# shell_2.net
KiCad netlist of a schematic drawn in EAGLE
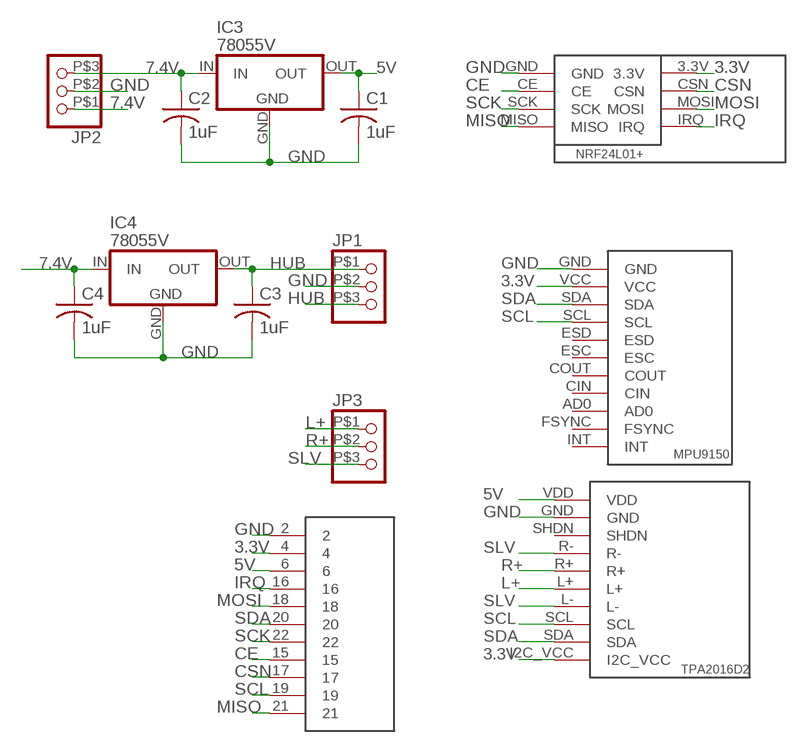
[diagram p0: schematic, sheet 1]

(export (version "E")
  (design (tool "Eeschema 10.0.6"))
  (components
    (comp (ref "C1")
      (value "1uF")
      (footprint "eagle-import:C050-024X044")
      (libsource (lib "eagle-import") (part "C-US050-024X044"))
    )
    (comp (ref "C2")
      (value "1uF")
      (footprint "eagle-import:C050-024X044")
      (libsource (lib "eagle-import") (part "C-US050-024X044"))
    )
    (comp (ref "C3")
      (value "1uF")
      (footprint "eagle-import:C050-024X044")
      (libsource (lib "eagle-import") (part "C-US050-024X044"))
    )
    (comp (ref "C4")
      (value "1uF")
      (footprint "eagle-import:C050-024X044")
      (libsource (lib "eagle-import") (part "C-US050-024X044"))
    )
    (comp (ref "IC3")
      (value "78055V")
      (footprint "eagle-import:TO220H")
      (libsource (lib "eagle-import") (part "785V05"))
    )
    (comp (ref "IC4")
      (value "78055V")
      (footprint "eagle-import:TO220H")
      (libsource (lib "eagle-import") (part "785V05"))
    )
    (comp (ref "JP1")
      (value "PINHD-1X3SMD")
      (footprint "eagle-import:1X3_90SMD")
      (libsource (lib "eagle-import") (part "PINHD-1X3SMD"))
    )
    (comp (ref "JP2")
      (value "PINHD-1X3SMD")
      (footprint "eagle-import:1X3_90SMD")
      (libsource (lib "eagle-import") (part "PINHD-1X3SMD"))
    )
    (comp (ref "JP3")
      (value "PINHD-1X3SMD")
      (footprint "eagle-import:1X3_90SMD")
      (libsource (lib "eagle-import") (part "PINHD-1X3SMD"))
    )
    (comp (ref "JP4")
      (value "PINHD-1X11SMD")
      (footprint "eagle-import:1X11_90_2")
      (libsource (lib "eagle-import") (part "PINHD-1X11SMD"))
    )
    (comp (ref "U$1")
      (value "MPU9150")
      (footprint "eagle-import:MPU9150")
      (libsource (lib "eagle-import") (part "MPU9150"))
    )
    (comp (ref "U$2")
      (value "NRF24L01")
      (footprint "eagle-import:NRF24L01")
      (libsource (lib "eagle-import") (part "NRF24L01"))
    )
    (comp (ref "U$3")
      (value "TPA2016D2")
      (footprint "eagle-import:TPA2016D2")
      (libsource (lib "eagle-import") (part "TPA2016D2"))
    )
  )
  (nets
    (net (code "1") (name "/3.3V") (class "Default")
      (node (ref "JP4") (pin "4") (pinfunction "4_4") (pintype "bidirectional"))
      (node (ref "U$1") (pin "VCC") (pinfunction "VCC_VCC") (pintype "bidirectional"))
      (node (ref "U$2") (pin "3.3V") (pinfunction "3.3V_3.3V") (pintype "bidirectional"))
      (node (ref "U$3") (pin "I2C_VCC") (pinfunction "I2C_VCC_I2C_VCC") (pintype "bidirectional"))
    )
    (net (code "2") (name "/5V") (class "Default")
      (node (ref "C1") (pin "1") (pinfunction "1_1") (pintype "passive"))
      (node (ref "IC3") (pin "OUT") (pinfunction "OUT_OUT") (pintype "passive"))
      (node (ref "JP4") (pin "6") (pinfunction "6_6") (pintype "bidirectional"))
      (node (ref "U$3") (pin "VDD") (pinfunction "VDD_VDD") (pintype "bidirectional"))
    )
    (net (code "3") (name "/7.4V") (class "Default")
      (node (ref "C2") (pin "1") (pinfunction "1_1") (pintype "passive"))
      (node (ref "C4") (pin "1") (pinfunction "1_1") (pintype "passive"))
      (node (ref "IC3") (pin "IN") (pinfunction "IN_IN") (pintype "input"))
      (node (ref "IC4") (pin "IN") (pinfunction "IN_IN") (pintype "input"))
      (node (ref "JP2") (pin "P$1") (pinfunction "1_P$1") (pintype "passive"))
      (node (ref "JP2") (pin "P$3") (pinfunction "3_P$3") (pintype "passive"))
    )
    (net (code "4") (name "/CE") (class "Default")
      (node (ref "JP4") (pin "15") (pinfunction "15_15") (pintype "bidirectional"))
      (node (ref "U$2") (pin "CE") (pinfunction "CE_CE") (pintype "bidirectional"))
    )
    (net (code "5") (name "/CSN") (class "Default")
      (node (ref "JP4") (pin "17") (pinfunction "17_17") (pintype "bidirectional"))
      (node (ref "U$2") (pin "CSN") (pinfunction "CSN_CSN") (pintype "bidirectional"))
    )
    (net (code "6") (name "/GND") (class "Default")
      (node (ref "C1") (pin "2") (pinfunction "2_2") (pintype "passive"))
      (node (ref "C2") (pin "2") (pinfunction "2_2") (pintype "passive"))
      (node (ref "C3") (pin "2") (pinfunction "2_2") (pintype "passive"))
      (node (ref "C4") (pin "2") (pinfunction "2_2") (pintype "passive"))
      (node (ref "IC3") (pin "GND") (pinfunction "GND_GND") (pintype "passive"))
      (node (ref "IC4") (pin "GND") (pinfunction "GND_GND") (pintype "passive"))
      (node (ref "JP1") (pin "P$2") (pinfunction "2_P$2") (pintype "passive"))
      (node (ref "JP2") (pin "P$2") (pinfunction "2_P$2") (pintype "passive"))
      (node (ref "JP4") (pin "2") (pinfunction "2_2") (pintype "bidirectional"))
      (node (ref "U$1") (pin "GND") (pinfunction "GND_GND") (pintype "bidirectional"))
      (node (ref "U$2") (pin "GND") (pinfunction "GND_GND") (pintype "bidirectional"))
      (node (ref "U$3") (pin "GND") (pinfunction "GND_GND") (pintype "bidirectional"))
    )
    (net (code "7") (name "/HUB") (class "Default")
      (node (ref "C3") (pin "1") (pinfunction "1_1") (pintype "passive"))
      (node (ref "IC4") (pin "OUT") (pinfunction "OUT_OUT") (pintype "passive"))
      (node (ref "JP1") (pin "P$1") (pinfunction "1_P$1") (pintype "passive"))
      (node (ref "JP1") (pin "P$3") (pinfunction "3_P$3") (pintype "passive"))
    )
    (net (code "8") (name "/IRQ") (class "Default")
      (node (ref "JP4") (pin "16") (pinfunction "16_16") (pintype "bidirectional"))
      (node (ref "U$2") (pin "IRQ") (pinfunction "IRQ_IRQ") (pintype "bidirectional"))
    )
    (net (code "9") (name "/L+") (class "Default")
      (node (ref "JP3") (pin "P$1") (pinfunction "1_P$1") (pintype "passive"))
      (node (ref "U$3") (pin "L+") (pinfunction "L+_L+") (pintype "bidirectional"))
    )
    (net (code "10") (name "/MISO") (class "Default")
      (node (ref "JP4") (pin "21") (pinfunction "21_21") (pintype "bidirectional"))
      (node (ref "U$2") (pin "MISO") (pinfunction "MISO_MISO") (pintype "bidirectional"))
    )
    (net (code "11") (name "/MOSI") (class "Default")
      (node (ref "JP4") (pin "18") (pinfunction "18_18") (pintype "bidirectional"))
      (node (ref "U$2") (pin "MOSI") (pinfunction "MOSI_MOSI") (pintype "bidirectional"))
    )
    (net (code "12") (name "/R+") (class "Default")
      (node (ref "JP3") (pin "P$2") (pinfunction "2_P$2") (pintype "passive"))
      (node (ref "U$3") (pin "R+") (pinfunction "R+_R+") (pintype "bidirectional"))
    )
    (net (code "13") (name "/SCK") (class "Default")
      (node (ref "JP4") (pin "22") (pinfunction "22_22") (pintype "bidirectional"))
      (node (ref "U$2") (pin "SCK") (pinfunction "SCK_SCK") (pintype "bidirectional"))
    )
    (net (code "14") (name "/SCL") (class "Default")
      (node (ref "JP4") (pin "19") (pinfunction "19_19") (pintype "bidirectional"))
      (node (ref "U$1") (pin "SCL") (pinfunction "SCL_SCL") (pintype "bidirectional"))
      (node (ref "U$3") (pin "SCL") (pinfunction "SCL_SCL") (pintype "bidirectional"))
    )
    (net (code "15") (name "/SDA") (class "Default")
      (node (ref "JP4") (pin "20") (pinfunction "20_20") (pintype "bidirectional"))
      (node (ref "U$1") (pin "SDA") (pinfunction "SDA_SDA") (pintype "bidirectional"))
      (node (ref "U$3") (pin "SDA") (pinfunction "SDA_SDA") (pintype "bidirectional"))
    )
    (net (code "16") (name "/SLV") (class "Default")
      (node (ref "JP3") (pin "P$3") (pinfunction "3_P$3") (pintype "passive"))
      (node (ref "U$3") (pin "L-") (pinfunction "L-_L-") (pintype "bidirectional"))
      (node (ref "U$3") (pin "R-") (pinfunction "R-_R-") (pintype "bidirectional"))
    )
    (net (code "17") (name "unconnected-(U$1-PadAD0)") (class "Default")
      (node (ref "U$1") (pin "AD0") (pinfunction "AD0_AD0") (pintype "bidirectional"))
    )
    (net (code "18") (name "unconnected-(U$1-PadCIN)") (class "Default")
      (node (ref "U$1") (pin "CIN") (pinfunction "CIN_CIN") (pintype "bidirectional"))
    )
    (net (code "19") (name "unconnected-(U$1-PadCOUT)") (class "Default")
      (node (ref "U$1") (pin "COUT") (pinfunction "COUT_COUT") (pintype "bidirectional"))
    )
    (net (code "20") (name "unconnected-(U$1-PadESC)") (class "Default")
      (node (ref "U$1") (pin "ESC") (pinfunction "ESC_ESC") (pintype "bidirectional"))
    )
    (net (code "21") (name "unconnected-(U$1-PadESD)") (class "Default")
      (node (ref "U$1") (pin "ESD") (pinfunction "ESD_ESD") (pintype "bidirectional"))
    )
    (net (code "22") (name "unconnected-(U$1-PadFSYNC)") (class "Default")
      (node (ref "U$1") (pin "FSYNC") (pinfunction "FSYNC_FSYNC") (pintype "bidirectional"))
    )
    (net (code "23") (name "unconnected-(U$1-PadINT)") (class "Default")
      (node (ref "U$1") (pin "INT") (pinfunction "INT_INT") (pintype "bidirectional"))
    )
    (net (code "24") (name "unconnected-(U$3-PadSHDN)") (class "Default")
      (node (ref "U$3") (pin "SHDN") (pinfunction "SHDN_SHDN") (pintype "bidirectional"))
    )
  )
)
